# untitled.net
KiCad netlist of a schematic drawn in EAGLE
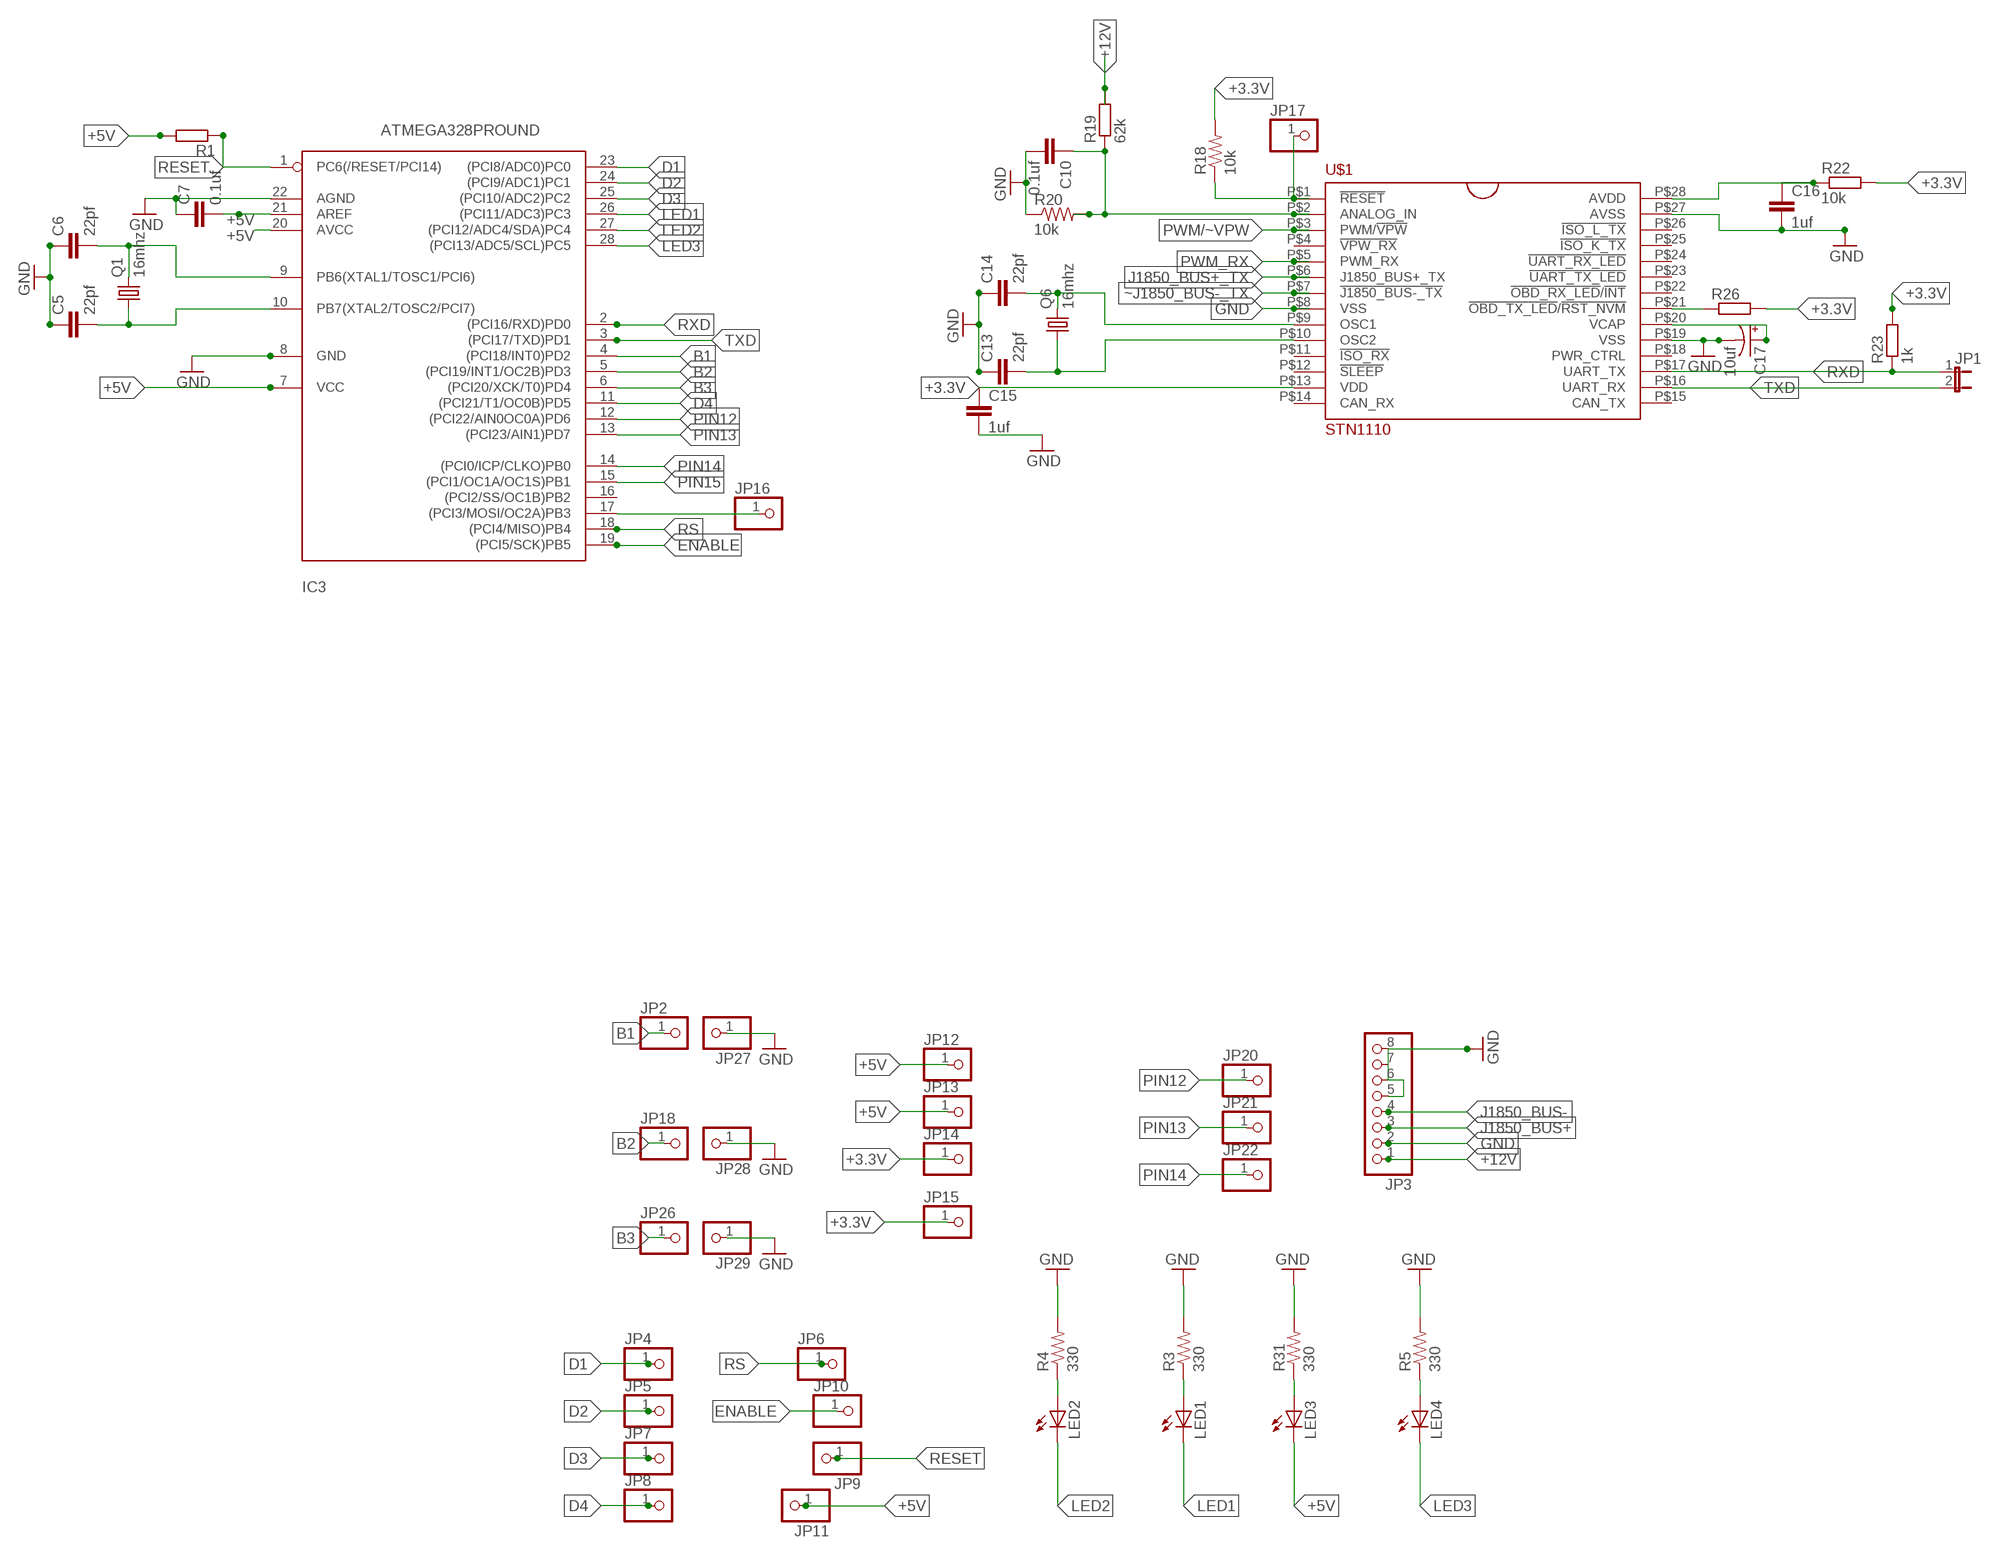
[diagram p0: schematic, sheet 1, part 1 of 2]
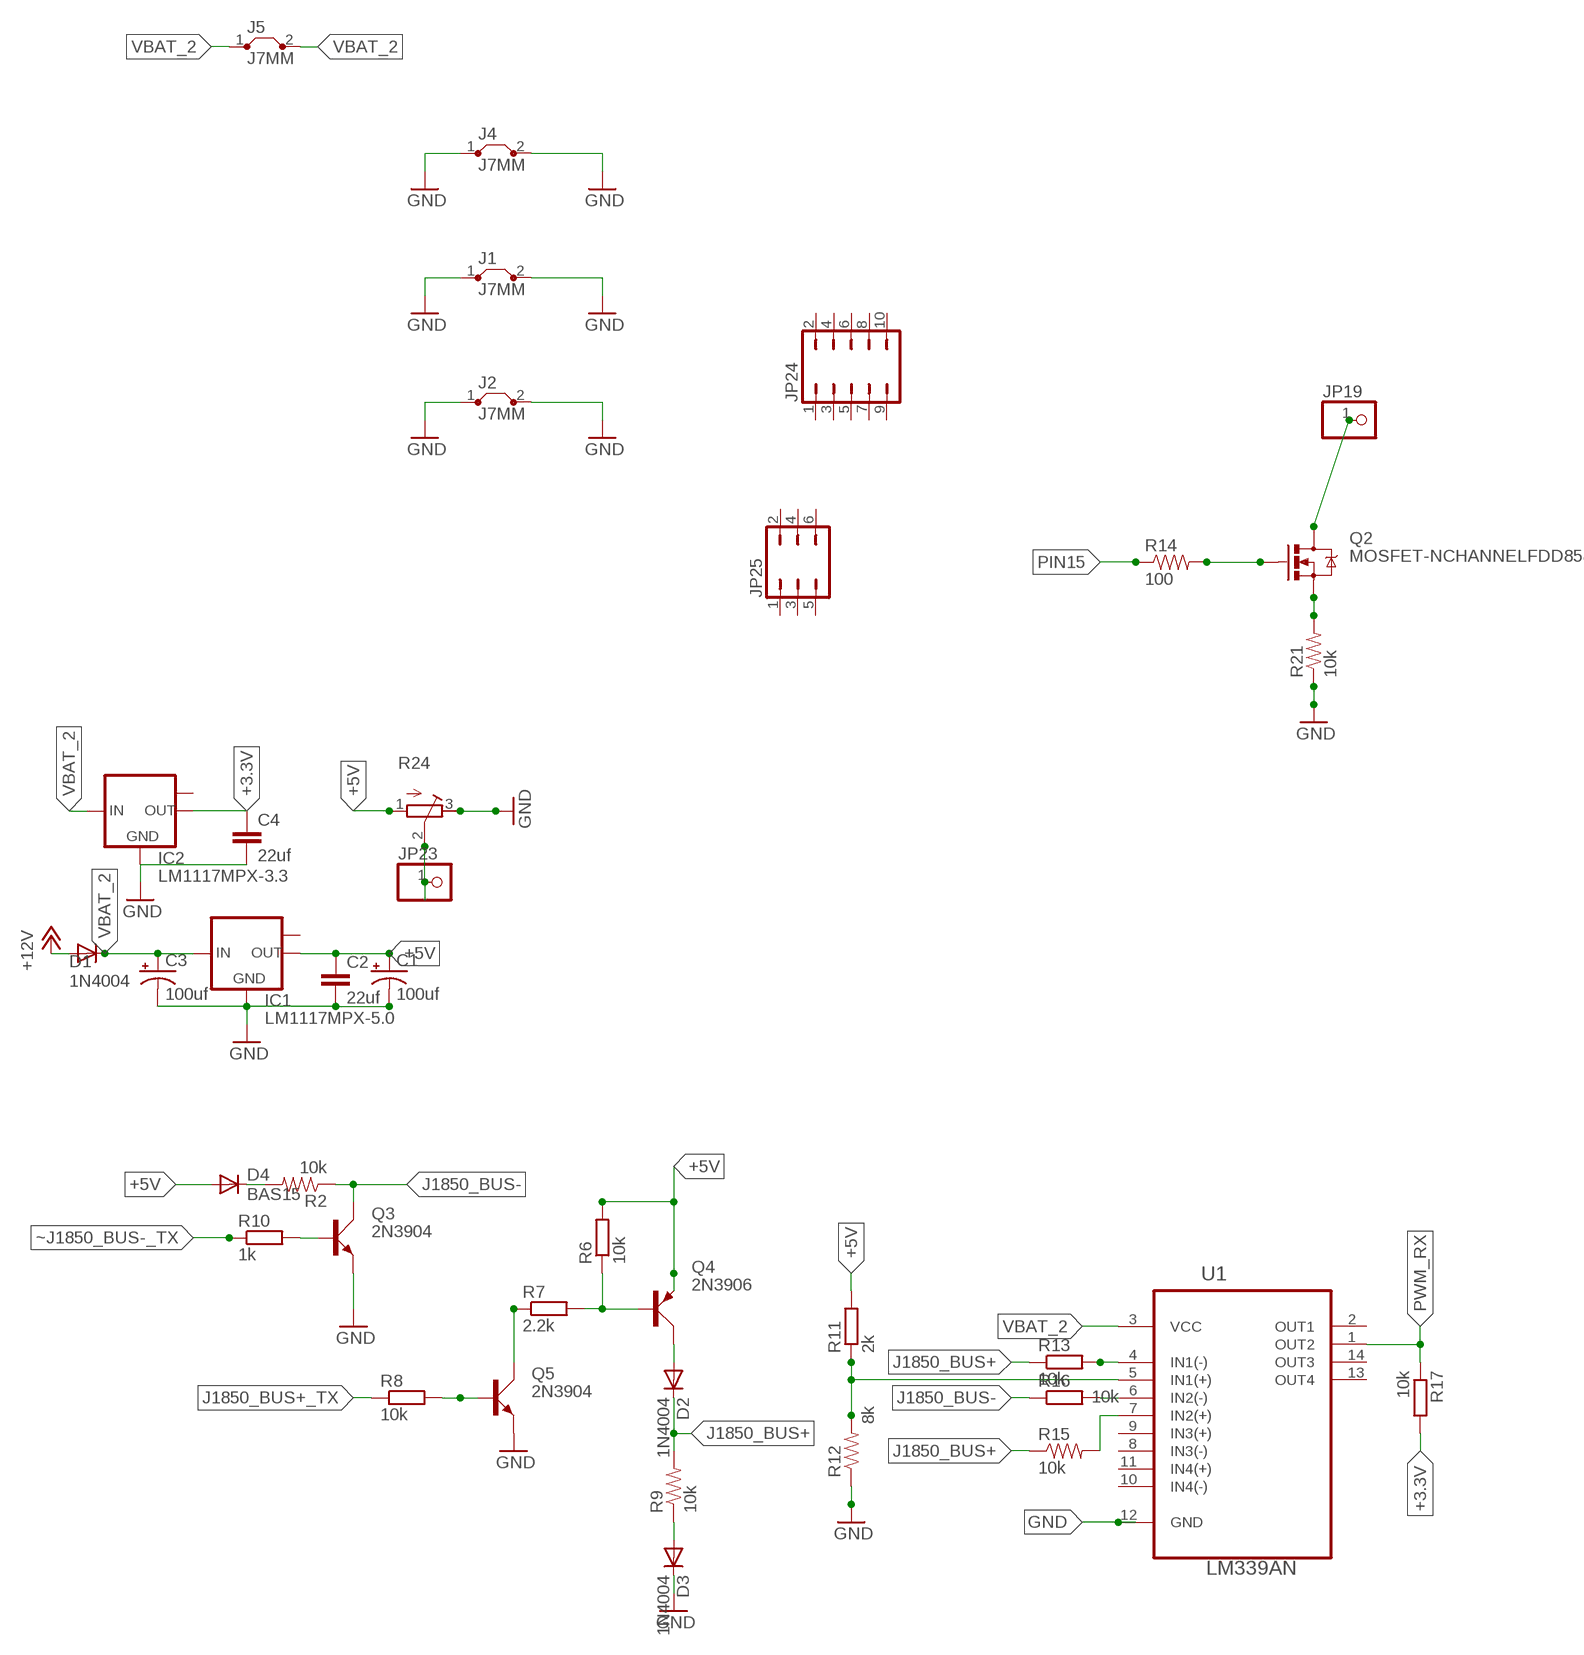
[diagram p1: schematic, sheet 1, part 2 of 2]

(export (version "E")
  (design (tool "Eeschema 10.0.6"))
  (components
    (comp (ref "C1")
      (value "100uf")
      (footprint "eagle-import:CPOL-RADIAL-10UF-25V-KIT")
      (libsource (lib "eagle-import") (part "10UF-25V-20%(PTH)KIT"))
    )
    (comp (ref "C2")
      (value "22uf")
      (footprint "eagle-import:C025-025X050")
      (libsource (lib "eagle-import") (part "C-EU025-025X050"))
    )
    (comp (ref "C3")
      (value "100uf")
      (footprint "eagle-import:CPOL-RADIAL-10UF-25V-KIT")
      (libsource (lib "eagle-import") (part "10UF-25V-20%(PTH)KIT"))
    )
    (comp (ref "C4")
      (value "22uf")
      (footprint "eagle-import:C025-025X050")
      (libsource (lib "eagle-import") (part "C-EU025-025X050"))
    )
    (comp (ref "C5")
      (value "22pf")
      (footprint "eagle-import:CAP-PTH-SMALL")
      (libsource (lib "eagle-import") (part "CAPPTH"))
    )
    (comp (ref "C6")
      (value "22pf")
      (footprint "eagle-import:CAP-PTH-SMALL")
      (libsource (lib "eagle-import") (part "CAPPTH"))
    )
    (comp (ref "C7")
      (value "0.1uf")
      (footprint "eagle-import:C5B4.5")
      (libsource (lib "eagle-import") (part "C5/4.5"))
    )
    (comp (ref "C10")
      (value "0.1uf")
      (footprint "eagle-import:C025-025X050")
      (libsource (lib "eagle-import") (part "C-EU025-025X050"))
    )
    (comp (ref "C13")
      (value "22pf")
      (footprint "eagle-import:CAP-PTH-SMALL")
      (libsource (lib "eagle-import") (part "CAPPTH"))
    )
    (comp (ref "C14")
      (value "22pf")
      (footprint "eagle-import:CAP-PTH-SMALL")
      (libsource (lib "eagle-import") (part "CAPPTH"))
    )
    (comp (ref "C15")
      (value "1uf")
      (footprint "eagle-import:C025-025X050")
      (libsource (lib "eagle-import") (part "C-EU025-025X050"))
    )
    (comp (ref "C16")
      (value "1uf")
      (footprint "eagle-import:C025-025X050")
      (libsource (lib "eagle-import") (part "C-EU025-025X050"))
    )
    (comp (ref "C17")
      (value "10uf")
      (footprint "eagle-import:CPOL-RADIAL-10UF-25V")
      (libsource (lib "eagle-import") (part "CAP_POLPTH2"))
    )
    (comp (ref "D1")
      (value "1N4004")
      (footprint "eagle-import:DO41-10")
      (libsource (lib "eagle-import") (part "1N4004"))
    )
    (comp (ref "D2")
      (value "1N4004")
      (footprint "eagle-import:DO41-10")
      (libsource (lib "eagle-import") (part "1N4004"))
    )
    (comp (ref "D3")
      (value "1N4004")
      (footprint "eagle-import:DO41-10")
      (libsource (lib "eagle-import") (part "1N4004"))
    )
    (comp (ref "D4")
      (value "BAS15")
      (footprint "eagle-import:DO34-7")
      (libsource (lib "eagle-import") (part "BAS15"))
    )
    (comp (ref "IC1")
      (value "LM1117MPX-5.0")
      (footprint "eagle-import:SOT223")
      (libsource (lib "eagle-import") (part "LM1117MPX-5.0"))
    )
    (comp (ref "IC2")
      (value "LM1117MPX-3.3")
      (footprint "eagle-import:SOT223")
      (libsource (lib "eagle-import") (part "LM1117MPX-3.3"))
    )
    (comp (ref "IC3")
      (value "ATMEGA328PROUND")
      (footprint "eagle-import:DIL28-3-ROUND")
      (libsource (lib "eagle-import") (part "ATMEGA328PROUND"))
    )
    (comp (ref "J1")
      (value "J7MM")
      (footprint "eagle-import:07")
      (libsource (lib "eagle-import") (part "J7MM"))
    )
    (comp (ref "J2")
      (value "J7MM")
      (footprint "eagle-import:07")
      (libsource (lib "eagle-import") (part "J7MM"))
    )
    (comp (ref "J4")
      (value "J7MM")
      (footprint "eagle-import:07")
      (libsource (lib "eagle-import") (part "J7MM"))
    )
    (comp (ref "J5")
      (value "J7MM")
      (footprint "eagle-import:07")
      (libsource (lib "eagle-import") (part "J7MM"))
    )
    (comp (ref "JP1")
      (value "JP1E")
      (footprint "eagle-import:JP1")
      (libsource (lib "eagle-import") (part "JP1E"))
    )
    (comp (ref "JP2")
      (value "PINHD-1X1")
      (footprint "eagle-import:1X01")
      (libsource (lib "eagle-import") (part "PINHD-1X1"))
    )
    (comp (ref "JP3")
      (value "PINHD-1X8")
      (footprint "eagle-import:1X08")
      (libsource (lib "eagle-import") (part "PINHD-1X8"))
    )
    (comp (ref "JP4")
      (value "PINHD-1X1")
      (footprint "eagle-import:1X01")
      (libsource (lib "eagle-import") (part "PINHD-1X1"))
    )
    (comp (ref "JP5")
      (value "PINHD-1X1")
      (footprint "eagle-import:1X01")
      (libsource (lib "eagle-import") (part "PINHD-1X1"))
    )
    (comp (ref "JP6")
      (value "PINHD-1X1")
      (footprint "eagle-import:1X01")
      (libsource (lib "eagle-import") (part "PINHD-1X1"))
    )
    (comp (ref "JP7")
      (value "PINHD-1X1")
      (footprint "eagle-import:1X01")
      (libsource (lib "eagle-import") (part "PINHD-1X1"))
    )
    (comp (ref "JP8")
      (value "PINHD-1X1")
      (footprint "eagle-import:1X01")
      (libsource (lib "eagle-import") (part "PINHD-1X1"))
    )
    (comp (ref "JP9")
      (value "PINHD-1X1")
      (footprint "eagle-import:1X01")
      (libsource (lib "eagle-import") (part "PINHD-1X1"))
    )
    (comp (ref "JP10")
      (value "PINHD-1X1")
      (footprint "eagle-import:1X01")
      (libsource (lib "eagle-import") (part "PINHD-1X1"))
    )
    (comp (ref "JP11")
      (value "PINHD-1X1")
      (footprint "eagle-import:1X01")
      (libsource (lib "eagle-import") (part "PINHD-1X1"))
    )
    (comp (ref "JP12")
      (value "PINHD-1X1")
      (footprint "eagle-import:1X01")
      (libsource (lib "eagle-import") (part "PINHD-1X1"))
    )
    (comp (ref "JP13")
      (value "PINHD-1X1")
      (footprint "eagle-import:1X01")
      (libsource (lib "eagle-import") (part "PINHD-1X1"))
    )
    (comp (ref "JP14")
      (value "PINHD-1X1")
      (footprint "eagle-import:1X01")
      (libsource (lib "eagle-import") (part "PINHD-1X1"))
    )
    (comp (ref "JP15")
      (value "PINHD-1X1")
      (footprint "eagle-import:1X01")
      (libsource (lib "eagle-import") (part "PINHD-1X1"))
    )
    (comp (ref "JP16")
      (value "PINHD-1X1")
      (footprint "eagle-import:1X01")
      (libsource (lib "eagle-import") (part "PINHD-1X1"))
    )
    (comp (ref "JP17")
      (value "PINHD-1X1")
      (footprint "eagle-import:1X01")
      (libsource (lib "eagle-import") (part "PINHD-1X1"))
    )
    (comp (ref "JP18")
      (value "PINHD-1X1")
      (footprint "eagle-import:1X01")
      (libsource (lib "eagle-import") (part "PINHD-1X1"))
    )
    (comp (ref "JP19")
      (value "PINHD-1X1")
      (footprint "eagle-import:1X01")
      (libsource (lib "eagle-import") (part "PINHD-1X1"))
    )
    (comp (ref "JP20")
      (value "PINHD-1X1")
      (footprint "eagle-import:1X01")
      (libsource (lib "eagle-import") (part "PINHD-1X1"))
    )
    (comp (ref "JP21")
      (value "PINHD-1X1")
      (footprint "eagle-import:1X01")
      (libsource (lib "eagle-import") (part "PINHD-1X1"))
    )
    (comp (ref "JP22")
      (value "PINHD-1X1")
      (footprint "eagle-import:1X01")
      (libsource (lib "eagle-import") (part "PINHD-1X1"))
    )
    (comp (ref "JP23")
      (value "PINHD-1X1")
      (footprint "eagle-import:1X01")
      (libsource (lib "eagle-import") (part "PINHD-1X1"))
    )
    (comp (ref "JP24")
      (value "JP5Q")
      (footprint "eagle-import:JP5Q")
      (libsource (lib "eagle-import") (part "JP5Q"))
    )
    (comp (ref "JP25")
      (value "JP3Q")
      (footprint "eagle-import:JP3Q")
      (libsource (lib "eagle-import") (part "JP3Q"))
    )
    (comp (ref "JP26")
      (value "PINHD-1X1")
      (footprint "eagle-import:1X01")
      (libsource (lib "eagle-import") (part "PINHD-1X1"))
    )
    (comp (ref "JP27")
      (value "PINHD-1X1")
      (footprint "eagle-import:1X01")
      (libsource (lib "eagle-import") (part "PINHD-1X1"))
    )
    (comp (ref "JP28")
      (value "PINHD-1X1")
      (footprint "eagle-import:1X01")
      (libsource (lib "eagle-import") (part "PINHD-1X1"))
    )
    (comp (ref "JP29")
      (value "PINHD-1X1")
      (footprint "eagle-import:1X01")
      (libsource (lib "eagle-import") (part "PINHD-1X1"))
    )
    (comp (ref "LED1")
      (value "LED3MM")
      (footprint "eagle-import:LED3MM")
      (libsource (lib "eagle-import") (part "LED3MM"))
    )
    (comp (ref "LED2")
      (value "LED3MM")
      (footprint "eagle-import:LED3MM")
      (libsource (lib "eagle-import") (part "LED3MM"))
    )
    (comp (ref "LED3")
      (value "LED5MM")
      (footprint "eagle-import:LED5MM")
      (libsource (lib "eagle-import") (part "LED5MM"))
    )
    (comp (ref "LED4")
      (value "LED3MM")
      (footprint "eagle-import:LED3MM")
      (libsource (lib "eagle-import") (part "LED3MM"))
    )
    (comp (ref "Q1")
      (value "16mhz")
      (footprint "eagle-import:HC49_S")
      (libsource (lib "eagle-import") (part "CRYSTALHC49S"))
    )
    (comp (ref "Q2")
      (value "MOSFET-NCHANNELFDD8580")
      (footprint "eagle-import:DPAK")
      (libsource (lib "eagle-import") (part "MOSFET-NCHANNELFDD8580"))
    )
    (comp (ref "Q3")
      (value "2N3904")
      (footprint "eagle-import:TO92D")
      (libsource (lib "eagle-import") (part "2N3904"))
    )
    (comp (ref "Q4")
      (value "2N3906")
      (footprint "eagle-import:TO92D")
      (libsource (lib "eagle-import") (part "2N3906"))
    )
    (comp (ref "Q5")
      (value "2N3904")
      (footprint "eagle-import:TO92D")
      (libsource (lib "eagle-import") (part "2N3904"))
    )
    (comp (ref "Q6")
      (value "16mhz")
      (footprint "eagle-import:HC49_S")
      (libsource (lib "eagle-import") (part "CRYSTALHC49S"))
    )
    (comp (ref "R1")
      (value "R-EU_0207/12")
      (footprint "eagle-import:0207_12")
      (libsource (lib "eagle-import") (part "resistor_R-EU_0207/12"))
    )
    (comp (ref "R2")
      (value "10k")
      (footprint "eagle-import:AXIAL-0.1EZ")
      (libsource (lib "eagle-import") (part "1KOHM-1/4W-1%(PTH)VERT-KIT"))
    )
    (comp (ref "R3")
      (value "330")
      (footprint "eagle-import:AXIAL-0.1EZ")
      (libsource (lib "eagle-import") (part "RESISTORPTH-1/4W-VERT-KIT"))
    )
    (comp (ref "R4")
      (value "330")
      (footprint "eagle-import:AXIAL-0.1EZ")
      (libsource (lib "eagle-import") (part "RESISTORPTH-1/4W-VERT-KIT"))
    )
    (comp (ref "R5")
      (value "330")
      (footprint "eagle-import:AXIAL-0.1EZ")
      (libsource (lib "eagle-import") (part "RESISTORPTH-1/4W-VERT-KIT"))
    )
    (comp (ref "R6")
      (value "10k")
      (footprint "eagle-import:0204_7")
      (libsource (lib "eagle-import") (part "R-EU_0204/7"))
    )
    (comp (ref "R7")
      (value "2.2k")
      (footprint "eagle-import:0207_12")
      (libsource (lib "eagle-import") (part "R-EU_0207/12"))
    )
    (comp (ref "R8")
      (value "10k")
      (footprint "eagle-import:0207_10")
      (libsource (lib "eagle-import") (part "R-EU_0207/10"))
    )
    (comp (ref "R9")
      (value "10k")
      (footprint "eagle-import:AXIAL-0.1EZ")
      (libsource (lib "eagle-import") (part "10KOHM-1/4W-1%(PTH)VERT-KIT"))
    )
    (comp (ref "R10")
      (value "1k")
      (footprint "eagle-import:0207_12")
      (libsource (lib "eagle-import") (part "R-EU_0207/12"))
    )
    (comp (ref "R11")
      (value "2k")
      (footprint "eagle-import:0207_10")
      (libsource (lib "eagle-import") (part "R-EU_0207/10"))
    )
    (comp (ref "R12")
      (value "8k")
      (footprint "eagle-import:AXIAL-0.1EZ")
      (libsource (lib "eagle-import") (part "10KOHM-1/4W5%(PTH)VERT-KIT"))
    )
    (comp (ref "R13")
      (value "10k")
      (footprint "eagle-import:0207_10")
      (libsource (lib "eagle-import") (part "R-EU_0207/10"))
    )
    (comp (ref "R14")
      (value "100")
      (footprint "eagle-import:AXIAL-0.1EZ")
      (libsource (lib "eagle-import") (part "10KOHM-1/4W-1%(PTH)VERT-KIT"))
    )
    (comp (ref "R15")
      (value "10k")
      (footprint "eagle-import:AXIAL-0.1EZ")
      (libsource (lib "eagle-import") (part "10KOHM-1/4W5%(PTH)VERT-KIT"))
    )
    (comp (ref "R16")
      (value "10k")
      (footprint "eagle-import:0207_10")
      (libsource (lib "eagle-import") (part "R-EU_0207/10"))
    )
    (comp (ref "R17")
      (value "10k")
      (footprint "eagle-import:0207_12")
      (libsource (lib "eagle-import") (part "R-EU_0207/12"))
    )
    (comp (ref "R18")
      (value "10k")
      (footprint "eagle-import:AXIAL-0.3EZ")
      (libsource (lib "eagle-import") (part "10KOHM-1/4W5%(PTH)HORIZ-KIT"))
    )
    (comp (ref "R19")
      (value "62k")
      (footprint "eagle-import:0207_12")
      (libsource (lib "eagle-import") (part "R-EU_0207/12"))
    )
    (comp (ref "R20")
      (value "10k")
      (footprint "eagle-import:AXIAL-0.1EZ")
      (libsource (lib "eagle-import") (part "1KOHM-1/4W-1%(PTH)VERT-KIT"))
    )
    (comp (ref "R21")
      (value "10k")
      (footprint "eagle-import:AXIAL-0.1EZ")
      (libsource (lib "eagle-import") (part "10KOHM-1/4W5%(PTH)VERT-KIT"))
    )
    (comp (ref "R22")
      (value "10k")
      (footprint "eagle-import:0204_7")
      (libsource (lib "eagle-import") (part "R-EU_0204/7"))
    )
    (comp (ref "R23")
      (value "1k")
      (footprint "eagle-import:0207_10")
      (libsource (lib "eagle-import") (part "R-EU_0207/10"))
    )
    (comp (ref "R24")
      (value "R-TRIMM74W")
      (footprint "eagle-import:RTRIM74W")
      (libsource (lib "eagle-import") (part "R-TRIMM74W"))
    )
    (comp (ref "R26")
      (value "R-EU_M3516")
      (footprint "eagle-import:M3516")
      (libsource (lib "eagle-import") (part "R-EU_M3516"))
    )
    (comp (ref "R31")
      (value "330")
      (footprint "eagle-import:AXIAL-0.1EZ")
      (libsource (lib "eagle-import") (part "RESISTORPTH-1/4W-VERT-KIT"))
    )
    (comp (ref "U$1")
      (value "STN1110")
      (footprint "eagle-import:SPDIP28")
      (libsource (lib "eagle-import") (part "STN1110"))
    )
    (comp (ref "U1")
      (value "LM339AN")
      (footprint "eagle-import:DIP254P762X508-14")
      (libsource (lib "eagle-import") (part "LM339AN"))
    )
  )
  (nets
    (net (code "1") (name "+3.3V") (class "Default")
      (node (ref "C15") (pin "1") (pinfunction "1_1") (pintype "passive"))
      (node (ref "C4") (pin "1") (pinfunction "1_1") (pintype "passive"))
      (node (ref "IC2") (pin "2") (pinfunction "OUT_2") (pintype "passive"))
      (node (ref "JP14") (pin "1") (pinfunction "1_1") (pintype "passive"))
      (node (ref "JP15") (pin "1") (pinfunction "1_1") (pintype "passive"))
      (node (ref "R17") (pin "2") (pinfunction "2_2") (pintype "passive"))
      (node (ref "R18") (pin "P$2") (pinfunction "2_P$2") (pintype "passive"))
      (node (ref "R22") (pin "2") (pinfunction "2_2") (pintype "passive"))
      (node (ref "R23") (pin "2") (pinfunction "2_2") (pintype "passive"))
      (node (ref "R26") (pin "2") (pinfunction "2_2") (pintype "passive"))
      (node (ref "U$1") (pin "P$13") (pinfunction "VDD_P$13") (pintype "bidirectional"))
    )
    (net (code "2") (name "+5V") (class "Default")
      (node (ref "C1") (pin "1") (pinfunction "+_1") (pintype "passive"))
      (node (ref "C2") (pin "1") (pinfunction "1_1") (pintype "passive"))
      (node (ref "C7") (pin "2") (pinfunction "2_2") (pintype "passive"))
      (node (ref "D4") (pin "A") (pinfunction "A_A") (pintype "passive"))
      (node (ref "IC1") (pin "2") (pinfunction "OUT_2") (pintype "passive"))
      (node (ref "IC3") (pin "20") (pinfunction "AVCC_20") (pintype "bidirectional"))
      (node (ref "IC3") (pin "21") (pinfunction "AREF_21") (pintype "bidirectional"))
      (node (ref "IC3") (pin "7") (pinfunction "VCC_7") (pintype "bidirectional"))
      (node (ref "JP11") (pin "1") (pinfunction "1_1") (pintype "passive"))
      (node (ref "JP12") (pin "1") (pinfunction "1_1") (pintype "passive"))
      (node (ref "JP13") (pin "1") (pinfunction "1_1") (pintype "passive"))
      (node (ref "LED3") (pin "K") (pinfunction "C_K") (pintype "passive"))
      (node (ref "Q4") (pin "E") (pinfunction "E_E") (pintype "passive"))
      (node (ref "R1") (pin "2") (pinfunction "2_2") (pintype "passive"))
      (node (ref "R11") (pin "2") (pinfunction "2_2") (pintype "passive"))
      (node (ref "R24") (pin "1") (pinfunction "E_1") (pintype "passive"))
      (node (ref "R6") (pin "2") (pinfunction "2_2") (pintype "passive"))
    )
    (net (code "3") (name "+12V") (class "Default")
      (node (ref "D1") (pin "A") (pinfunction "A_A") (pintype "passive"))
      (node (ref "JP3") (pin "1") (pinfunction "1_1") (pintype "passive"))
      (node (ref "R19") (pin "2") (pinfunction "2_2") (pintype "passive"))
    )
    (net (code "4") (name "/PWM{slash}~{VPW}") (class "Default")
      (node (ref "U$1") (pin "P$3") (pinfunction "PWM/~{VPW}_P$3") (pintype "bidirectional"))
    )
    (net (code "5") (name "/~{J1850_BUS-_TX}") (class "Default")
      (node (ref "R10") (pin "1") (pinfunction "1_1") (pintype "passive"))
      (node (ref "U$1") (pin "P$7") (pinfunction "~{J1850_BUS-_TX}_P$7") (pintype "bidirectional"))
    )
    (net (code "6") (name "B1") (class "Default")
      (node (ref "IC3") (pin "4") (pinfunction "(PCI18/INT0)PD2_4") (pintype "bidirectional"))
      (node (ref "JP2") (pin "1") (pinfunction "1_1") (pintype "passive"))
    )
    (net (code "7") (name "B2") (class "Default")
      (node (ref "IC3") (pin "5") (pinfunction "(PCI19/INT1/OC2B)PD3_5") (pintype "bidirectional"))
      (node (ref "JP18") (pin "1") (pinfunction "1_1") (pintype "passive"))
    )
    (net (code "8") (name "B3") (class "Default")
      (node (ref "IC3") (pin "6") (pinfunction "(PCI20/XCK/T0)PD4_6") (pintype "bidirectional"))
      (node (ref "JP26") (pin "1") (pinfunction "1_1") (pintype "passive"))
    )
    (net (code "9") (name "D1") (class "Default")
      (node (ref "IC3") (pin "23") (pinfunction "(PCI8/ADC0)PC0_23") (pintype "bidirectional"))
      (node (ref "JP4") (pin "1") (pinfunction "1_1") (pintype "passive"))
    )
    (net (code "10") (name "D2") (class "Default")
      (node (ref "IC3") (pin "24") (pinfunction "(PCI9/ADC1)PC1_24") (pintype "bidirectional"))
      (node (ref "JP5") (pin "1") (pinfunction "1_1") (pintype "passive"))
    )
    (net (code "11") (name "D3") (class "Default")
      (node (ref "IC3") (pin "25") (pinfunction "(PCI10/ADC2)PC2_25") (pintype "bidirectional"))
      (node (ref "JP7") (pin "1") (pinfunction "1_1") (pintype "passive"))
    )
    (net (code "12") (name "D4") (class "Default")
      (node (ref "IC3") (pin "11") (pinfunction "(PCI21/T1/OC0B)PD5_11") (pintype "bidirectional"))
      (node (ref "JP8") (pin "1") (pinfunction "1_1") (pintype "passive"))
    )
    (net (code "13") (name "ENABLE") (class "Default")
      (node (ref "IC3") (pin "19") (pinfunction "(PCI5/SCK)PB5_19") (pintype "bidirectional"))
      (node (ref "JP10") (pin "1") (pinfunction "1_1") (pintype "passive"))
    )
    (net (code "14") (name "GND") (class "Default")
      (node (ref "C1") (pin "2") (pinfunction "-_2") (pintype "passive"))
      (node (ref "C10") (pin "2") (pinfunction "2_2") (pintype "passive"))
      (node (ref "C13") (pin "1") (pinfunction "1_1") (pintype "passive"))
      (node (ref "C14") (pin "1") (pinfunction "1_1") (pintype "passive"))
      (node (ref "C15") (pin "2") (pinfunction "2_2") (pintype "passive"))
      (node (ref "C16") (pin "2") (pinfunction "2_2") (pintype "passive"))
      (node (ref "C17") (pin "2") (pinfunction "-_2") (pintype "passive"))
      (node (ref "C2") (pin "2") (pinfunction "2_2") (pintype "passive"))
      (node (ref "C3") (pin "2") (pinfunction "-_2") (pintype "passive"))
      (node (ref "C4") (pin "2") (pinfunction "2_2") (pintype "passive"))
      (node (ref "C5") (pin "1") (pinfunction "1_1") (pintype "passive"))
      (node (ref "C6") (pin "1") (pinfunction "1_1") (pintype "passive"))
      (node (ref "C7") (pin "1") (pinfunction "1_1") (pintype "passive"))
      (node (ref "D3") (pin "C") (pinfunction "C_C") (pintype "passive"))
      (node (ref "IC1") (pin "1") (pinfunction "GND_1") (pintype "input"))
      (node (ref "IC2") (pin "1") (pinfunction "GND_1") (pintype "input"))
      (node (ref "IC3") (pin "22") (pinfunction "AGND_22") (pintype "bidirectional"))
      (node (ref "IC3") (pin "8") (pinfunction "GND_8") (pintype "bidirectional"))
      (node (ref "J1") (pin "1") (pinfunction "1_1") (pintype "passive"))
      (node (ref "J1") (pin "2") (pinfunction "2_2") (pintype "passive"))
      (node (ref "J2") (pin "1") (pinfunction "1_1") (pintype "passive"))
      (node (ref "J2") (pin "2") (pinfunction "2_2") (pintype "passive"))
      (node (ref "J4") (pin "1") (pinfunction "1_1") (pintype "passive"))
      (node (ref "J4") (pin "2") (pinfunction "2_2") (pintype "passive"))
      (node (ref "JP27") (pin "1") (pinfunction "1_1") (pintype "passive"))
      (node (ref "JP28") (pin "1") (pinfunction "1_1") (pintype "passive"))
      (node (ref "JP29") (pin "1") (pinfunction "1_1") (pintype "passive"))
      (node (ref "JP3") (pin "2") (pinfunction "2_2") (pintype "passive"))
      (node (ref "JP3") (pin "5") (pinfunction "5_5") (pintype "passive"))
      (node (ref "JP3") (pin "6") (pinfunction "6_6") (pintype "passive"))
      (node (ref "JP3") (pin "7") (pinfunction "7_7") (pintype "passive"))
      (node (ref "JP3") (pin "8") (pinfunction "8_8") (pintype "passive"))
      (node (ref "Q3") (pin "E") (pinfunction "E_E") (pintype "passive"))
      (node (ref "Q5") (pin "E") (pinfunction "E_E") (pintype "passive"))
      (node (ref "R12") (pin "P$1") (pinfunction "1_P$1") (pintype "passive"))
      (node (ref "R20") (pin "P$1") (pinfunction "1_P$1") (pintype "passive"))
      (node (ref "R21") (pin "P$1") (pinfunction "1_P$1") (pintype "passive"))
      (node (ref "R24") (pin "3") (pinfunction "A_3") (pintype "passive"))
      (node (ref "R3") (pin "P$2") (pinfunction "2_P$2") (pintype "passive"))
      (node (ref "R31") (pin "P$2") (pinfunction "2_P$2") (pintype "passive"))
      (node (ref "R4") (pin "P$2") (pinfunction "2_P$2") (pintype "passive"))
      (node (ref "R5") (pin "P$2") (pinfunction "2_P$2") (pintype "passive"))
      (node (ref "U$1") (pin "P$19") (pinfunction "VSS_P$19") (pintype "bidirectional"))
      (node (ref "U$1") (pin "P$27") (pinfunction "AVSS_P$27") (pintype "bidirectional"))
      (node (ref "U$1") (pin "P$8") (pinfunction "VSS_P$8") (pintype "bidirectional"))
      (node (ref "U1") (pin "12") (pinfunction "GND_12") (pintype "passive"))
    )
    (net (code "15") (name "J1850_BUS+") (class "Default")
      (node (ref "D2") (pin "C") (pinfunction "C_C") (pintype "passive"))
      (node (ref "JP3") (pin "3") (pinfunction "3_3") (pintype "passive"))
      (node (ref "R13") (pin "1") (pinfunction "1_1") (pintype "passive"))
      (node (ref "R15") (pin "P$1") (pinfunction "1_P$1") (pintype "passive"))
      (node (ref "R9") (pin "P$2") (pinfunction "2_P$2") (pintype "passive"))
    )
    (net (code "16") (name "J1850_BUS+_TX") (class "Default")
      (node (ref "R8") (pin "1") (pinfunction "1_1") (pintype "passive"))
      (node (ref "U$1") (pin "P$6") (pinfunction "J1850_BUS+_TX_P$6") (pintype "bidirectional"))
    )
    (net (code "17") (name "J1850_BUS-") (class "Default")
      (node (ref "JP3") (pin "4") (pinfunction "4_4") (pintype "passive"))
      (node (ref "Q3") (pin "C") (pinfunction "C_C") (pintype "passive"))
      (node (ref "R16") (pin "1") (pinfunction "1_1") (pintype "passive"))
      (node (ref "R2") (pin "P$1") (pinfunction "1_P$1") (pintype "passive"))
    )
    (net (code "18") (name "LED1") (class "Default")
      (node (ref "IC3") (pin "26") (pinfunction "(PCI11/ADC3)PC3_26") (pintype "bidirectional"))
      (node (ref "LED1") (pin "K") (pinfunction "C_K") (pintype "passive"))
    )
    (net (code "19") (name "LED2") (class "Default")
      (node (ref "IC3") (pin "27") (pinfunction "(PCI12/ADC4/SDA)PC4_27") (pintype "bidirectional"))
      (node (ref "LED2") (pin "K") (pinfunction "C_K") (pintype "passive"))
    )
    (net (code "20") (name "LED3") (class "Default")
      (node (ref "IC3") (pin "28") (pinfunction "(PCI13/ADC5/SCL)PC5_28") (pintype "bidirectional"))
      (node (ref "LED4") (pin "K") (pinfunction "C_K") (pintype "passive"))
    )
    (net (code "21") (name "Net-(C17-+)") (class "Default")
      (node (ref "C17") (pin "1") (pinfunction "+_1") (pintype "passive"))
      (node (ref "U$1") (pin "P$20") (pinfunction "VCAP_P$20") (pintype "bidirectional"))
    )
    (net (code "22") (name "Net-(D2-PadA)") (class "Default")
      (node (ref "D2") (pin "A") (pinfunction "A_A") (pintype "passive"))
      (node (ref "Q4") (pin "C") (pinfunction "C_C") (pintype "passive"))
    )
    (net (code "23") (name "Net-(IC3-(PCI3{slash}MOSI{slash}OC2A)PB3)") (class "Default")
      (node (ref "IC3") (pin "17") (pinfunction "(PCI3/MOSI/OC2A)PB3_17") (pintype "bidirectional"))
      (node (ref "JP16") (pin "1") (pinfunction "1_1") (pintype "passive"))
    )
    (net (code "24") (name "Net-(IC3-PB6(XTAL1{slash}TOSC1{slash}PCI6))") (class "Default")
      (node (ref "C6") (pin "2") (pinfunction "2_2") (pintype "passive"))
      (node (ref "IC3") (pin "9") (pinfunction "PB6(XTAL1/TOSC1/PCI6)_9") (pintype "bidirectional"))
      (node (ref "Q1") (pin "2") (pinfunction "2_2") (pintype "passive"))
    )
    (net (code "25") (name "Net-(IC3-PB7(XTAL2{slash}TOSC2{slash}PCI7))") (class "Default")
      (node (ref "C5") (pin "2") (pinfunction "2_2") (pintype "passive"))
      (node (ref "IC3") (pin "10") (pinfunction "PB7(XTAL2/TOSC2/PCI7)_10") (pintype "bidirectional"))
      (node (ref "Q1") (pin "1") (pinfunction "1_1") (pintype "passive"))
    )
    (net (code "26") (name "Net-(Q2-D)") (class "Default")
      (node (ref "JP19") (pin "1") (pinfunction "1_1") (pintype "passive"))
      (node (ref "Q2") (pin "4") (pinfunction "D_4") (pintype "passive"))
    )
    (net (code "27") (name "Net-(Q2-G)") (class "Default")
      (node (ref "Q2") (pin "1") (pinfunction "G_1") (pintype "passive"))
      (node (ref "R14") (pin "P$2") (pinfunction "2_P$2") (pintype "passive"))
    )
    (net (code "28") (name "Net-(Q2-S)") (class "Default")
      (node (ref "Q2") (pin "3") (pinfunction "S_3") (pintype "passive"))
      (node (ref "R21") (pin "P$2") (pinfunction "2_P$2") (pintype "passive"))
    )
    (net (code "29") (name "Net-(Q3-PadB)") (class "Default")
      (node (ref "Q3") (pin "B") (pinfunction "B_B") (pintype "passive"))
      (node (ref "R10") (pin "2") (pinfunction "2_2") (pintype "passive"))
    )
    (net (code "30") (name "Net-(Q4-PadB)") (class "Default")
      (node (ref "Q4") (pin "B") (pinfunction "B_B") (pintype "passive"))
      (node (ref "R6") (pin "1") (pinfunction "1_1") (pintype "passive"))
      (node (ref "R7") (pin "2") (pinfunction "2_2") (pintype "passive"))
    )
    (net (code "31") (name "Net-(Q5-PadB)") (class "Default")
      (node (ref "Q5") (pin "B") (pinfunction "B_B") (pintype "passive"))
      (node (ref "R8") (pin "2") (pinfunction "2_2") (pintype "passive"))
    )
    (net (code "32") (name "Net-(Q5-PadC)") (class "Default")
      (node (ref "Q5") (pin "C") (pinfunction "C_C") (pintype "passive"))
      (node (ref "R7") (pin "1") (pinfunction "1_1") (pintype "passive"))
    )
    (net (code "33") (name "Net-(R2-2)") (class "Default")
      (node (ref "D4") (pin "C") (pinfunction "C_C") (pintype "passive"))
      (node (ref "R2") (pin "P$2") (pinfunction "2_P$2") (pintype "passive"))
    )
    (net (code "34") (name "Net-(R3-1)") (class "Default")
      (node (ref "LED1") (pin "A") (pinfunction "A_A") (pintype "passive"))
      (node (ref "R3") (pin "P$1") (pinfunction "1_P$1") (pintype "passive"))
    )
    (net (code "35") (name "Net-(R4-1)") (class "Default")
      (node (ref "LED2") (pin "A") (pinfunction "A_A") (pintype "passive"))
      (node (ref "R4") (pin "P$1") (pinfunction "1_P$1") (pintype "passive"))
    )
    (net (code "36") (name "Net-(R5-1)") (class "Default")
      (node (ref "LED4") (pin "A") (pinfunction "A_A") (pintype "passive"))
      (node (ref "R5") (pin "P$1") (pinfunction "1_P$1") (pintype "passive"))
    )
    (net (code "37") (name "Net-(R9-1)") (class "Default")
      (node (ref "D3") (pin "A") (pinfunction "A_A") (pintype "passive"))
      (node (ref "R9") (pin "P$1") (pinfunction "1_P$1") (pintype "passive"))
    )
    (net (code "38") (name "Net-(R12-2)") (class "Default")
      (node (ref "R11") (pin "1") (pinfunction "1_1") (pintype "passive"))
      (node (ref "R12") (pin "P$2") (pinfunction "2_P$2") (pintype "passive"))
      (node (ref "U1") (pin "5") (pinfunction "IN1(+)_5") (pintype "input"))
    )
    (net (code "39") (name "Net-(R15-2)") (class "Default")
      (node (ref "R15") (pin "P$2") (pinfunction "2_P$2") (pintype "passive"))
      (node (ref "U1") (pin "7") (pinfunction "IN2(+)_7") (pintype "input"))
    )
    (net (code "40") (name "Net-(R18-1)") (class "Default")
      (node (ref "JP17") (pin "1") (pinfunction "1_1") (pintype "passive"))
      (node (ref "R18") (pin "P$1") (pinfunction "1_P$1") (pintype "passive"))
      (node (ref "U$1") (pin "P$1") (pinfunction "~{RESET}_P$1") (pintype "bidirectional"))
    )
    (net (code "41") (name "Net-(R20-2)") (class "Default")
      (node (ref "C10") (pin "1") (pinfunction "1_1") (pintype "passive"))
      (node (ref "R19") (pin "1") (pinfunction "1_1") (pintype "passive"))
      (node (ref "R20") (pin "P$2") (pinfunction "2_P$2") (pintype "passive"))
      (node (ref "U$1") (pin "P$2") (pinfunction "ANALOG_IN_P$2") (pintype "bidirectional"))
    )
    (net (code "42") (name "Net-(R24-S)") (class "Default")
      (node (ref "JP23") (pin "1") (pinfunction "1_1") (pintype "passive"))
      (node (ref "R24") (pin "2") (pinfunction "S_2") (pintype "passive"))
    )
    (net (code "43") (name "Net-(R31-1)") (class "Default")
      (node (ref "LED3") (pin "A") (pinfunction "A_A") (pintype "passive"))
      (node (ref "R31") (pin "P$1") (pinfunction "1_P$1") (pintype "passive"))
    )
    (net (code "44") (name "Net-(U$1-AVDD)") (class "Default")
      (node (ref "C16") (pin "1") (pinfunction "1_1") (pintype "passive"))
      (node (ref "R22") (pin "1") (pinfunction "1_1") (pintype "passive"))
      (node (ref "U$1") (pin "P$28") (pinfunction "AVDD_P$28") (pintype "bidirectional"))
    )
    (net (code "45") (name "Net-(U$1-OSC1)") (class "Default")
      (node (ref "C14") (pin "2") (pinfunction "2_2") (pintype "passive"))
      (node (ref "Q6") (pin "2") (pinfunction "2_2") (pintype "passive"))
      (node (ref "U$1") (pin "P$9") (pinfunction "OSC1_P$9") (pintype "bidirectional"))
    )
    (net (code "46") (name "Net-(U$1-OSC2)") (class "Default")
      (node (ref "C13") (pin "2") (pinfunction "2_2") (pintype "passive"))
      (node (ref "Q6") (pin "1") (pinfunction "1_1") (pintype "passive"))
      (node (ref "U$1") (pin "P$10") (pinfunction "OSC2_P$10") (pintype "bidirectional"))
    )
    (net (code "47") (name "Net-(U$1-~{OBD_TX_LED}{slash}~{RST_NVM})") (class "Default")
      (node (ref "R26") (pin "1") (pinfunction "1_1") (pintype "passive"))
      (node (ref "U$1") (pin "P$21") (pinfunction "~{OBD_TX_LED}/~{RST_NVM}_P$21") (pintype "bidirectional"))
    )
    (net (code "48") (name "Net-(U1-IN1(-))") (class "Default")
      (node (ref "R13") (pin "2") (pinfunction "2_2") (pintype "passive"))
      (node (ref "U1") (pin "4") (pinfunction "IN1(-)_4") (pintype "input"))
    )
    (net (code "49") (name "Net-(U1-IN2(-))") (class "Default")
      (node (ref "R16") (pin "2") (pinfunction "2_2") (pintype "passive"))
      (node (ref "U1") (pin "6") (pinfunction "IN2(-)_6") (pintype "input"))
    )
    (net (code "50") (name "PIN12") (class "Default")
      (node (ref "IC3") (pin "12") (pinfunction "(PCI22/AIN0OC0A)PD6_12") (pintype "bidirectional"))
      (node (ref "JP20") (pin "1") (pinfunction "1_1") (pintype "passive"))
    )
    (net (code "51") (name "PIN13") (class "Default")
      (node (ref "IC3") (pin "13") (pinfunction "(PCI23/AIN1)PD7_13") (pintype "bidirectional"))
      (node (ref "JP21") (pin "1") (pinfunction "1_1") (pintype "passive"))
    )
    (net (code "52") (name "PIN14") (class "Default")
      (node (ref "IC3") (pin "14") (pinfunction "(PCI0/ICP/CLKO)PB0_14") (pintype "bidirectional"))
      (node (ref "JP22") (pin "1") (pinfunction "1_1") (pintype "passive"))
    )
    (net (code "53") (name "PIN15") (class "Default")
      (node (ref "IC3") (pin "15") (pinfunction "(PCI1/OC1A/OC1S)PB1_15") (pintype "bidirectional"))
      (node (ref "R14") (pin "P$1") (pinfunction "1_P$1") (pintype "passive"))
    )
    (net (code "54") (name "PWM_RX") (class "Default")
      (node (ref "R17") (pin "1") (pinfunction "1_1") (pintype "passive"))
      (node (ref "U$1") (pin "P$5") (pinfunction "PWM_RX_P$5") (pintype "bidirectional"))
      (node (ref "U1") (pin "1") (pinfunction "OUT2_1") (pintype "output"))
    )
    (net (code "55") (name "RESET") (class "Default")
      (node (ref "IC3") (pin "1") (pinfunction "PC6(/RESET/PCI14)_1") (pintype "bidirectional"))
      (node (ref "JP9") (pin "1") (pinfunction "1_1") (pintype "passive"))
      (node (ref "R1") (pin "1") (pinfunction "1_1") (pintype "passive"))
    )
    (net (code "56") (name "RS") (class "Default")
      (node (ref "IC3") (pin "18") (pinfunction "(PCI4/MISO)PB4_18") (pintype "bidirectional"))
      (node (ref "JP6") (pin "1") (pinfunction "1_1") (pintype "passive"))
    )
    (net (code "57") (name "RXD") (class "Default")
      (node (ref "IC3") (pin "2") (pinfunction "(PCI16/RXD)PD0_2") (pintype "bidirectional"))
      (node (ref "JP1") (pin "1") (pinfunction "1_1") (pintype "passive"))
      (node (ref "R23") (pin "1") (pinfunction "1_1") (pintype "passive"))
      (node (ref "U$1") (pin "P$17") (pinfunction "UART_TX_P$17") (pintype "bidirectional"))
    )
    (net (code "58") (name "TXD") (class "Default")
      (node (ref "IC3") (pin "3") (pinfunction "(PCI17/TXD)PD1_3") (pintype "bidirectional"))
      (node (ref "JP1") (pin "2") (pinfunction "2_2") (pintype "passive"))
      (node (ref "U$1") (pin "P$16") (pinfunction "UART_RX_P$16") (pintype "bidirectional"))
    )
    (net (code "59") (name "VBAT_2") (class "Default")
      (node (ref "C3") (pin "1") (pinfunction "+_1") (pintype "passive"))
      (node (ref "D1") (pin "C") (pinfunction "C_C") (pintype "passive"))
      (node (ref "IC1") (pin "3") (pinfunction "IN_3") (pintype "input"))
      (node (ref "IC2") (pin "3") (pinfunction "IN_3") (pintype "input"))
      (node (ref "J5") (pin "1") (pinfunction "1_1") (pintype "passive"))
      (node (ref "J5") (pin "2") (pinfunction "2_2") (pintype "passive"))
      (node (ref "U1") (pin "3") (pinfunction "VCC_3") (pintype "power_in"))
    )
    (net (code "60") (name "unconnected-(IC1-OUT1-PadTAB)") (class "Default")
      (node (ref "IC1") (pin "TAB") (pinfunction "OUT1_TAB") (pintype "passive"))
    )
    (net (code "61") (name "unconnected-(IC2-OUT1-PadTAB)") (class "Default")
      (node (ref "IC2") (pin "TAB") (pinfunction "OUT1_TAB") (pintype "passive"))
    )
    (net (code "62") (name "unconnected-(IC3-(PCI2{slash}SS{slash}OC1B)PB2-Pad16)") (class "Default")
      (node (ref "IC3") (pin "16") (pinfunction "(PCI2/SS/OC1B)PB2_16") (pintype "bidirectional"))
    )
    (net (code "63") (name "unconnected-(JP24-Pad1)") (class "Default")
      (node (ref "JP24") (pin "1") (pinfunction "1_1") (pintype "passive"))
    )
    (net (code "64") (name "unconnected-(JP24-Pad2)") (class "Default")
      (node (ref "JP24") (pin "2") (pinfunction "2_2") (pintype "passive"))
    )
    (net (code "65") (name "unconnected-(JP24-Pad3)") (class "Default")
      (node (ref "JP24") (pin "3") (pinfunction "3_3") (pintype "passive"))
    )
    (net (code "66") (name "unconnected-(JP24-Pad4)") (class "Default")
      (node (ref "JP24") (pin "4") (pinfunction "4_4") (pintype "passive"))
    )
    (net (code "67") (name "unconnected-(JP24-Pad5)") (class "Default")
      (node (ref "JP24") (pin "5") (pinfunction "5_5") (pintype "passive"))
    )
    (net (code "68") (name "unconnected-(JP24-Pad6)") (class "Default")
      (node (ref "JP24") (pin "6") (pinfunction "6_6") (pintype "passive"))
    )
    (net (code "69") (name "unconnected-(JP24-Pad7)") (class "Default")
      (node (ref "JP24") (pin "7") (pinfunction "7_7") (pintype "passive"))
    )
    (net (code "70") (name "unconnected-(JP24-Pad8)") (class "Default")
      (node (ref "JP24") (pin "8") (pinfunction "8_8") (pintype "passive"))
    )
    (net (code "71") (name "unconnected-(JP24-Pad9)") (class "Default")
      (node (ref "JP24") (pin "9") (pinfunction "9_9") (pintype "passive"))
    )
    (net (code "72") (name "unconnected-(JP24-Pad10)") (class "Default")
      (node (ref "JP24") (pin "10") (pinfunction "10_10") (pintype "passive"))
    )
    (net (code "73") (name "unconnected-(JP25-Pad1)") (class "Default")
      (node (ref "JP25") (pin "1") (pinfunction "1_1") (pintype "passive"))
    )
    (net (code "74") (name "unconnected-(JP25-Pad2)") (class "Default")
      (node (ref "JP25") (pin "2") (pinfunction "2_2") (pintype "passive"))
    )
    (net (code "75") (name "unconnected-(JP25-Pad3)") (class "Default")
      (node (ref "JP25") (pin "3") (pinfunction "3_3") (pintype "passive"))
    )
    (net (code "76") (name "unconnected-(JP25-Pad4)") (class "Default")
      (node (ref "JP25") (pin "4") (pinfunction "4_4") (pintype "passive"))
    )
    (net (code "77") (name "unconnected-(JP25-Pad5)") (class "Default")
      (node (ref "JP25") (pin "5") (pinfunction "5_5") (pintype "passive"))
    )
    (net (code "78") (name "unconnected-(JP25-Pad6)") (class "Default")
      (node (ref "JP25") (pin "6") (pinfunction "6_6") (pintype "passive"))
    )
    (net (code "79") (name "unconnected-(U$1-CAN_RX-PadP$14)") (class "Default")
      (node (ref "U$1") (pin "P$14") (pinfunction "CAN_RX_P$14") (pintype "bidirectional"))
    )
    (net (code "80") (name "unconnected-(U$1-CAN_TX-PadP$15)") (class "Default")
      (node (ref "U$1") (pin "P$15") (pinfunction "CAN_TX_P$15") (pintype "bidirectional"))
    )
    (net (code "81") (name "unconnected-(U$1-PWR_CTRL-PadP$18)") (class "Default")
      (node (ref "U$1") (pin "P$18") (pinfunction "PWR_CTRL_P$18") (pintype "bidirectional"))
    )
    (net (code "82") (name "unconnected-(U$1-~{ISO_K_TX}-PadP$25)") (class "Default")
      (node (ref "U$1") (pin "P$25") (pinfunction "~{ISO_K_TX}_P$25") (pintype "bidirectional"))
    )
    (net (code "83") (name "unconnected-(U$1-~{ISO_L_TX}-PadP$26)") (class "Default")
      (node (ref "U$1") (pin "P$26") (pinfunction "~{ISO_L_TX}_P$26") (pintype "bidirectional"))
    )
    (net (code "84") (name "unconnected-(U$1-~{ISO_RX}-PadP$11)") (class "Default")
      (node (ref "U$1") (pin "P$11") (pinfunction "~{ISO_RX}_P$11") (pintype "bidirectional"))
    )
    (net (code "85") (name "unconnected-(U$1-~{OBD_RX_LED}{slash}~{INT}-PadP$22)") (class "Default")
      (node (ref "U$1") (pin "P$22") (pinfunction "~{OBD_RX_LED}/~{INT}_P$22") (pintype "bidirectional"))
    )
    (net (code "86") (name "unconnected-(U$1-~{SLEEP}-PadP$12)") (class "Default")
      (node (ref "U$1") (pin "P$12") (pinfunction "~{SLEEP}_P$12") (pintype "bidirectional"))
    )
    (net (code "87") (name "unconnected-(U$1-~{UART_RX_LED}-PadP$24)") (class "Default")
      (node (ref "U$1") (pin "P$24") (pinfunction "~{UART_RX_LED}_P$24") (pintype "bidirectional"))
    )
    (net (code "88") (name "unconnected-(U$1-~{UART_TX_LED}-PadP$23)") (class "Default")
      (node (ref "U$1") (pin "P$23") (pinfunction "~{UART_TX_LED}_P$23") (pintype "bidirectional"))
    )
    (net (code "89") (name "unconnected-(U$1-~{VPW_RX}-PadP$4)") (class "Default")
      (node (ref "U$1") (pin "P$4") (pinfunction "~{VPW_RX}_P$4") (pintype "bidirectional"))
    )
    (net (code "90") (name "unconnected-(U1-IN3(+)-Pad9)") (class "Default")
      (node (ref "U1") (pin "9") (pinfunction "IN3(+)_9") (pintype "input"))
    )
    (net (code "91") (name "unconnected-(U1-IN3(-)-Pad8)") (class "Default")
      (node (ref "U1") (pin "8") (pinfunction "IN3(-)_8") (pintype "input"))
    )
    (net (code "92") (name "unconnected-(U1-IN4(+)-Pad11)") (class "Default")
      (node (ref "U1") (pin "11") (pinfunction "IN4(+)_11") (pintype "input"))
    )
    (net (code "93") (name "unconnected-(U1-IN4(-)-Pad10)") (class "Default")
      (node (ref "U1") (pin "10") (pinfunction "IN4(-)_10") (pintype "input"))
    )
    (net (code "94") (name "unconnected-(U1-OUT1-Pad2)") (class "Default")
      (node (ref "U1") (pin "2") (pinfunction "OUT1_2") (pintype "output"))
    )
    (net (code "95") (name "unconnected-(U1-OUT3-Pad14)") (class "Default")
      (node (ref "U1") (pin "14") (pinfunction "OUT3_14") (pintype "output"))
    )
    (net (code "96") (name "unconnected-(U1-OUT4-Pad13)") (class "Default")
      (node (ref "U1") (pin "13") (pinfunction "OUT4_13") (pintype "output"))
    )
  )
)
